# R2D.net
KiCad netlist of a schematic drawn in Altium Designer
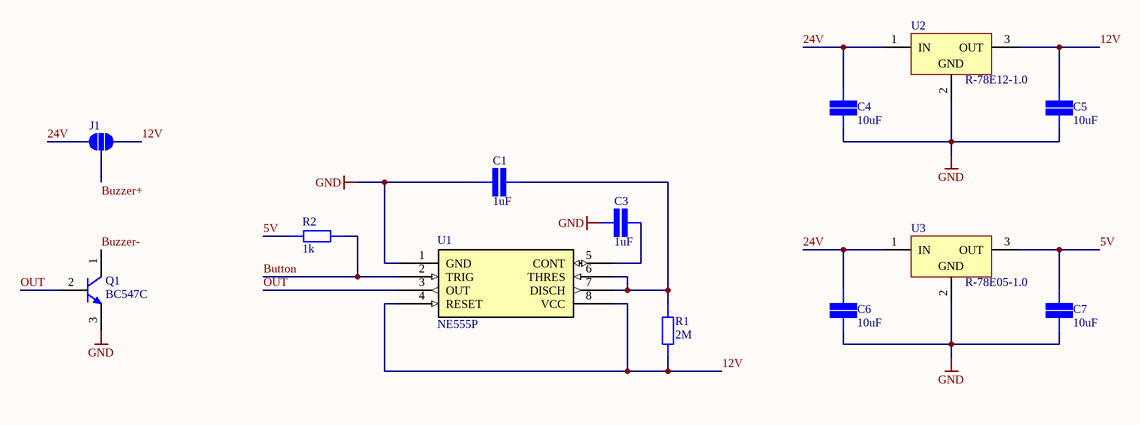
[diagram p0: R2D.SchDoc]

(export (version "E")
  (design (tool "Eeschema 10.0.6"))
  (components
    (comp (ref "C1")
      (value "1uF")
      (footprint "CAP 0603/1608")
      (description "Capacitor with multiple Footprints")
      (fields (field (name "Comment") "SMD Capacitor"))
      (libsource (lib "") (part "SMD Capacitor_1"))
    )
    (comp (ref "C3")
      (value "1uF")
      (footprint "CAP 0603/1608")
      (description "Capacitor with multiple Footprints")
      (fields (field (name "Comment") "SMD Capacitor"))
      (libsource (lib "") (part "SMD Capacitor_1"))
    )
    (comp (ref "C4")
      (value "10uF")
      (footprint "CAP 0603/1608")
      (description "Capacitor with multiple Footprints")
      (fields (field (name "Comment") "SMD Capacitor"))
      (libsource (lib "Standardbauteile") (part "SMD Capacitor"))
    )
    (comp (ref "C5")
      (value "10uF")
      (footprint "CAP 0603/1608")
      (description "Capacitor with multiple Footprints")
      (fields (field (name "Comment") "SMD Capacitor"))
      (libsource (lib "Standardbauteile") (part "SMD Capacitor"))
    )
    (comp (ref "C6")
      (value "10uF")
      (footprint "CAP 0603/1608")
      (description "Capacitor with multiple Footprints")
      (fields (field (name "Comment") "SMD Capacitor"))
      (libsource (lib "Standardbauteile") (part "SMD Capacitor"))
    )
    (comp (ref "C7")
      (value "10uF")
      (footprint "CAP 0603/1608")
      (description "Capacitor with multiple Footprints")
      (fields (field (name "Comment") "SMD Capacitor"))
      (libsource (lib "Standardbauteile") (part "SMD Capacitor"))
    )
    (comp (ref "J1")
      (value "JUMPERID")
      (footprint "SMD-JUMPER-3")
      (libsource (lib "Standardbauteile") (part "SMD Jumper 3"))
    )
    (comp (ref "Q1")
      (value "BC547C")
      (footprint "ONSC-TO-92-3-29-11")
      (description "Amplifier Transistor, NPN Silicon, 3-Pin TO-92, Bulk Box")
      (fields (field (name "MANUFACTURER") "On Semiconductor"))
      (libsource (lib "Altium Content Vault") (part "ONSC-NPN-C1B2E3-3"))
    )
    (comp (ref "R1")
      (value "2M")
      (footprint "STACKPOLE CSR0603")
      (description "Resistor with multiple footprints")
      (fields (field (name "Comment") "SMD Resistor"))
      (libsource (lib "Standardbauteile") (part "SMD Resistor"))
    )
    (comp (ref "R2")
      (value "1k")
      (footprint "STACKPOLE CSR0603")
      (description "Resistor with multiple footprints")
      (fields (field (name "Comment") "SMD Resistor"))
      (libsource (lib "Standardbauteile") (part "SMD Resistor"))
    )
    (comp (ref "U1")
      (value "NE555P")
      (footprint "NE555P")
      (description "Zeitgeber")
      (libsource (lib "LibMoritz") (part "NE555P"))
    )
    (comp (ref "U2")
      (value "R-78E12-1.0")
      (footprint "SIP3_RECOM")
      (description "Nonisolated 5V Switchmode converter")
      (libsource (lib "Standardbauteile") (part "R-78E05-1.0"))
    )
    (comp (ref "U3")
      (value "R-78E05-1.0")
      (footprint "SIP3_RECOM")
      (description "Nonisolated 5V Switchmode converter")
      (libsource (lib "Standardbauteile") (part "R-78E05-1.0"))
    )
  )
  (nets
    (net (code "1") (name "/5V") (class "Default")
      (node (ref "C7") (pin "1") (pinfunction "1_1") (pintype "passive"))
      (node (ref "R2") (pin "2") (pinfunction "2_2") (pintype "passive"))
      (node (ref "U3") (pin "3") (pinfunction "OUT_3") (pintype "power_in"))
    )
    (net (code "2") (name "/12V") (class "Default")
      (node (ref "C5") (pin "1") (pinfunction "1_1") (pintype "passive"))
      (node (ref "J1") (pin "1") (pinfunction "1_1") (pintype "passive"))
      (node (ref "R1") (pin "1") (pinfunction "1_1") (pintype "passive"))
      (node (ref "U1") (pin "4") (pinfunction "RESET_4") (pintype "input"))
      (node (ref "U1") (pin "8") (pinfunction "VCC_8") (pintype "passive"))
      (node (ref "U2") (pin "3") (pinfunction "OUT_3") (pintype "power_in"))
    )
    (net (code "3") (name "/24V") (class "Default")
      (node (ref "C4") (pin "1") (pinfunction "1_1") (pintype "passive"))
      (node (ref "C6") (pin "1") (pinfunction "1_1") (pintype "passive"))
      (node (ref "J1") (pin "3") (pinfunction "3_3") (pintype "passive"))
      (node (ref "U2") (pin "1") (pinfunction "IN_1") (pintype "power_in"))
      (node (ref "U3") (pin "1") (pinfunction "IN_1") (pintype "power_in"))
    )
    (net (code "4") (name "/Button") (class "Default")
      (node (ref "R2") (pin "1") (pinfunction "1_1") (pintype "passive"))
      (node (ref "U1") (pin "2") (pinfunction "TRIG_2") (pintype "input"))
    )
    (net (code "5") (name "/Buzzer+") (class "Default")
      (node (ref "J1") (pin "2") (pinfunction "2_2") (pintype "passive"))
    )
    (net (code "6") (name "/Buzzer-") (class "Default")
      (node (ref "Q1") (pin "1") (pinfunction "C_1") (pintype "passive"))
    )
    (net (code "7") (name "/OUT") (class "Default")
      (node (ref "Q1") (pin "2") (pinfunction "B_2") (pintype "passive"))
      (node (ref "U1") (pin "3") (pinfunction "OUT_3") (pintype "output"))
    )
    (net (code "8") (name "GND") (class "Default")
      (node (ref "C1") (pin "2") (pinfunction "2_2") (pintype "passive"))
      (node (ref "C3") (pin "2") (pinfunction "2_2") (pintype "passive"))
      (node (ref "C4") (pin "2") (pinfunction "2_2") (pintype "passive"))
      (node (ref "C5") (pin "2") (pinfunction "2_2") (pintype "passive"))
      (node (ref "C6") (pin "2") (pinfunction "2_2") (pintype "passive"))
      (node (ref "C7") (pin "2") (pinfunction "2_2") (pintype "passive"))
      (node (ref "Q1") (pin "3") (pinfunction "E_3") (pintype "passive"))
      (node (ref "U1") (pin "1") (pinfunction "GND_1") (pintype "passive"))
      (node (ref "U2") (pin "2") (pinfunction "GND_2") (pintype "power_in"))
      (node (ref "U3") (pin "2") (pinfunction "GND_2") (pintype "power_in"))
    )
    (net (code "9") (name "Net-(U1-CONT)") (class "Default")
      (node (ref "C3") (pin "1") (pinfunction "1_1") (pintype "passive"))
      (node (ref "U1") (pin "5") (pinfunction "CONT_5") (pintype "bidirectional"))
    )
    (net (code "10") (name "Net-(U1-DISCH)") (class "Default")
      (node (ref "C1") (pin "1") (pinfunction "1_1") (pintype "passive"))
      (node (ref "R1") (pin "2") (pinfunction "2_2") (pintype "passive"))
      (node (ref "U1") (pin "6") (pinfunction "THRES_6") (pintype "input"))
      (node (ref "U1") (pin "7") (pinfunction "DISCH_7") (pintype "output"))
    )
  )
)
